# LPCB218_-_LIFT_MECH_RELAY.net
KiCad netlist of a schematic drawn in Altium Designer
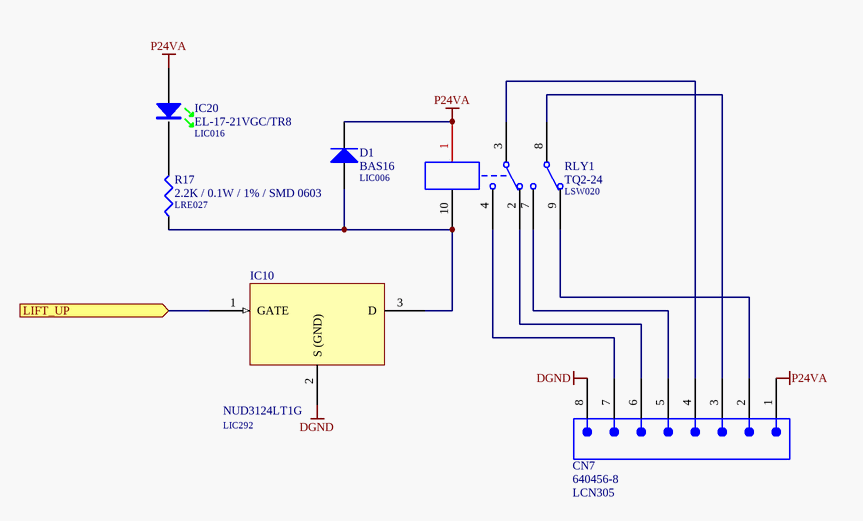
[diagram p0: LPCB218 - LIFT MECH RELAY.SchDoc]

(export (version "E")
  (design (tool "Eeschema 10.0.6"))
  (components
    (comp (ref "CN7")
      (value "640456-8")
      (footprint "640456-8")
      (description "Connector, Male Header, 8 Way")
      (fields (field (name "LDL_NUMBER") "LCN305"))
      (libsource (lib "LDL_Connectors") (part "640456-8"))
    )
    (comp (ref "D1")
      (value "BAS16")
      (footprint "LFP021__SOT23")
      (description "Diode, Small Signal, 0.2A, 85V, SMD SOT-23 [LIC006]")
      (fields (field (name "LDL_NUMBER") "LIC006"))
      (libsource (lib "LDL_Semiconductors") (part "BAS16"))
    )
    (comp (ref "IC10")
      (value "NUD3124LT1G")
      (footprint "LFP021__SOT23")
      (description "IC, Relay Driver, 28V Industrial, SMD SOT23 [LIC292]")
      (fields (field (name "LDL_NUMBER") "LIC292"))
      (libsource (lib "LDL_Semiconductors") (part "NUD3124LT1G"))
    )
    (comp (ref "IC20")
      (value "EL-17-21VGC/TR8")
      (footprint "CR2012-0805-LED")
      (description "LED, SMD, 0805 Green [LIC016]")
      (fields (field (name "LDL_NUMBER") "LIC016"))
      (libsource (lib "LDL_Semiconductors") (part "EL-17-21VGC/TR8"))
    )
    (comp (ref "R17")
      (value "2.2K / 0.1W / 1% / SMD 0603")
      (footprint "LFP020__CR1608-0603-IPC7351_B")
      (description "Resistor, Ceramic Chip, 2.2K, 0.1W, 1%, SMD 0603 [LRE027]")
      (fields (field (name "LDL_NUMBER") "LRE027"))
      (libsource (lib "LDL_Resistors") (part "2.2K / 0.1W / 1% / SMD 0603"))
    )
    (comp (ref "RLY1")
      (value "TQ2-24")
      (footprint "TQ2")
      (description "Relay, DPDT, Non Latching, 24VDC Coil, 1A Rating, PTH")
      (fields (field (name "LDL_NUMBER") "LSW020"))
      (libsource (lib "LDL_Switching") (part "TQ2-24"))
    )
  )
  (nets
    (net (code "1") (name "/LIFT_UP") (class "Default")
      (node (ref "IC10") (pin "1") (pinfunction "GATE_1") (pintype "input"))
    )
    (net (code "2") (name "DGND") (class "Default")
      (node (ref "CN7") (pin "8") (pinfunction "8_8") (pintype "passive"))
      (node (ref "IC10") (pin "2") (pinfunction "S_(GND)_2") (pintype "passive"))
    )
    (net (code "3") (name "Net-(CN7-Pad2)") (class "Default")
      (node (ref "CN7") (pin "2") (pinfunction "2_2") (pintype "passive"))
      (node (ref "RLY1") (pin "9") (pinfunction "9_9") (pintype "passive"))
    )
    (net (code "4") (name "Net-(CN7-Pad3)") (class "Default")
      (node (ref "CN7") (pin "3") (pinfunction "3_3") (pintype "passive"))
      (node (ref "RLY1") (pin "8") (pinfunction "8_8") (pintype "passive"))
    )
    (net (code "5") (name "Net-(CN7-Pad4)") (class "Default")
      (node (ref "CN7") (pin "4") (pinfunction "4_4") (pintype "passive"))
      (node (ref "RLY1") (pin "3") (pinfunction "3_3") (pintype "passive"))
    )
    (net (code "6") (name "Net-(CN7-Pad5)") (class "Default")
      (node (ref "CN7") (pin "5") (pinfunction "5_5") (pintype "passive"))
      (node (ref "RLY1") (pin "7") (pinfunction "7_7") (pintype "passive"))
    )
    (net (code "7") (name "Net-(CN7-Pad6)") (class "Default")
      (node (ref "CN7") (pin "6") (pinfunction "6_6") (pintype "passive"))
      (node (ref "RLY1") (pin "2") (pinfunction "2_2") (pintype "passive"))
    )
    (net (code "8") (name "Net-(CN7-Pad7)") (class "Default")
      (node (ref "CN7") (pin "7") (pinfunction "7_7") (pintype "passive"))
      (node (ref "RLY1") (pin "4") (pinfunction "4_4") (pintype "passive"))
    )
    (net (code "9") (name "Net-(D1-A)") (class "Default")
      (node (ref "D1") (pin "1") (pinfunction "A_1") (pintype "passive"))
      (node (ref "IC10") (pin "3") (pinfunction "D_3") (pintype "passive"))
      (node (ref "R17") (pin "1") (pintype "passive"))
      (node (ref "RLY1") (pin "10") (pinfunction "10_10") (pintype "passive"))
    )
    (net (code "10") (name "Net-(IC20-PadK)") (class "Default")
      (node (ref "IC20") (pin "K") (pintype "passive"))
      (node (ref "R17") (pin "2") (pintype "passive"))
    )
    (net (code "11") (name "P24VA") (class "Default")
      (node (ref "CN7") (pin "1") (pinfunction "1_1") (pintype "passive"))
      (node (ref "D1") (pin "3") (pinfunction "K_3") (pintype "passive"))
      (node (ref "IC20") (pin "A") (pintype "passive"))
      (node (ref "RLY1") (pin "1") (pinfunction "1_1") (pintype "passive"))
    )
  )
)
